# SCH_Emisor.net
KiCad netlist of a schematic drawn in EasyEDA
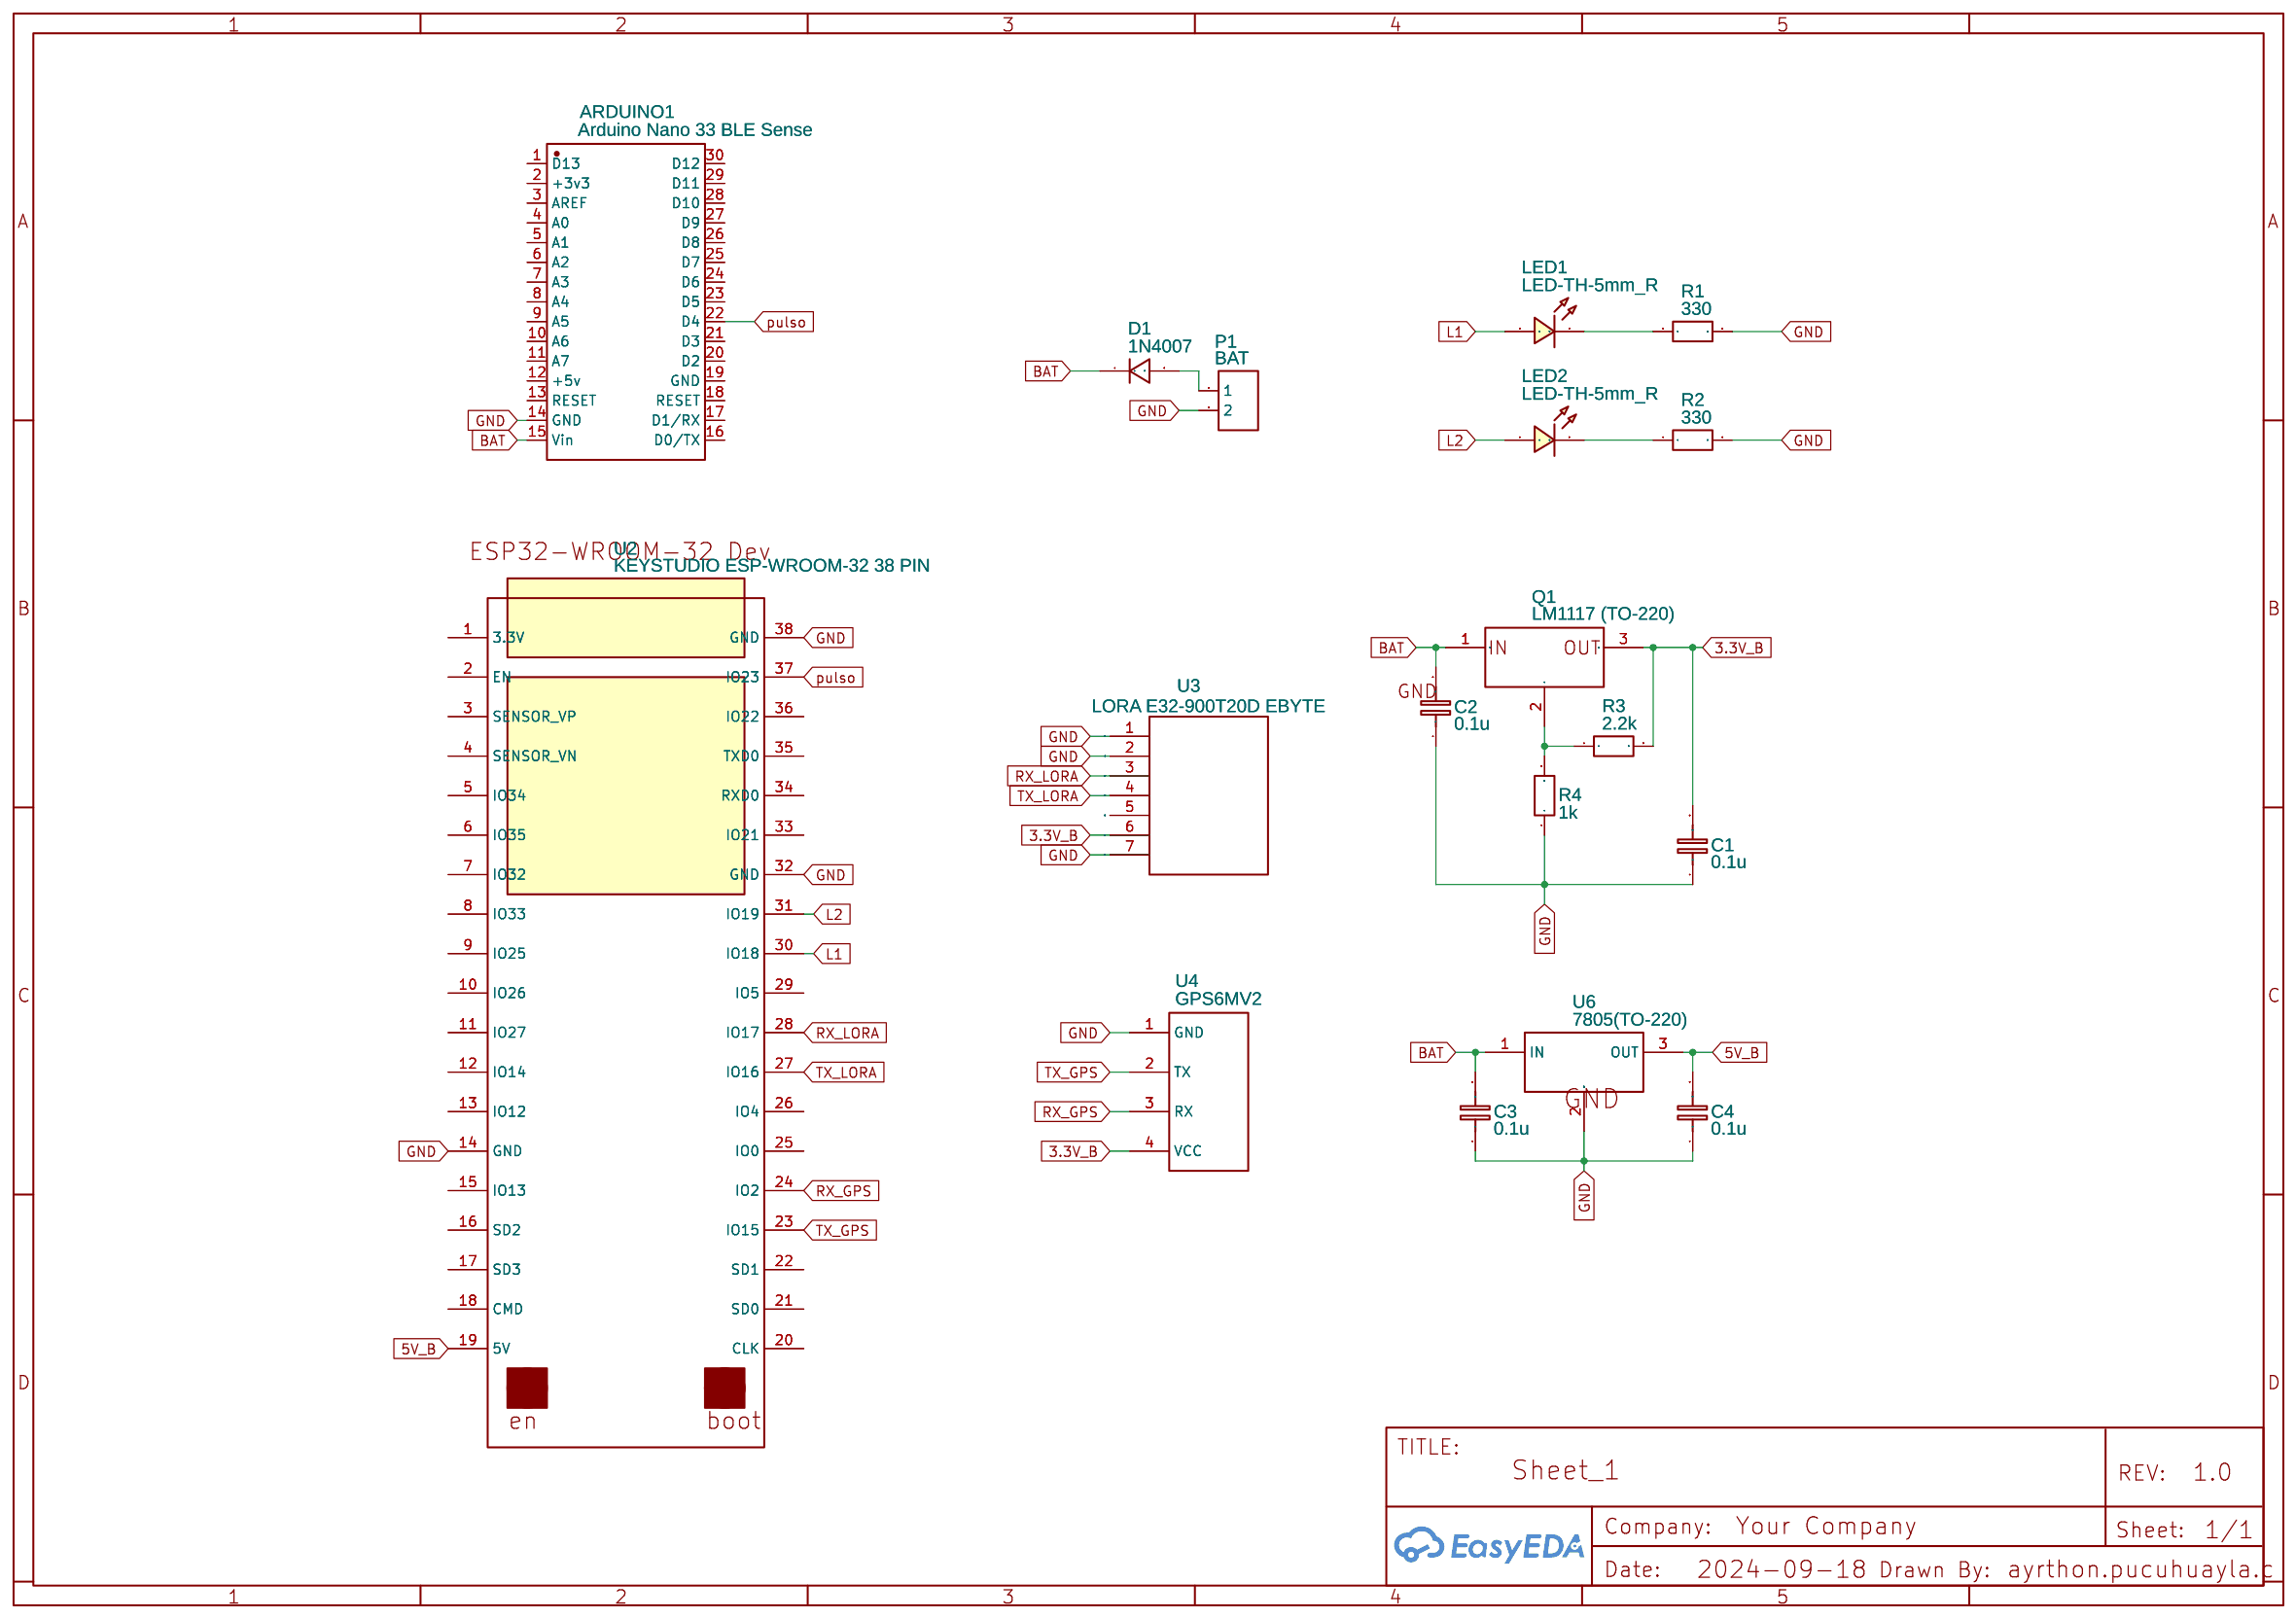
[diagram p0: schematic sheet]

(export (version "E")
  (design (tool "Eeschema 10.0.6"))
  (components
    (comp (ref "ARDUINO1")
      (value "Arduino Nano 33 BLE Sense")
      (libsource (lib "") (part "Arduino Nano 33 BLE Sense"))
    )
    (comp (ref "C1") (value "0.1u") (libsource (lib "") (part "C_RAD-0.1_EU")))
    (comp (ref "C2") (value "0.1u") (libsource (lib "") (part "C_RAD-0.1_EU")))
    (comp (ref "C3") (value "0.1u") (libsource (lib "") (part "C_RAD-0.1_EU")))
    (comp (ref "C4") (value "0.1u") (libsource (lib "") (part "C_RAD-0.1_EU")))
    (comp (ref "D1")
      (value "1N4007")
      (fields (field (name "Manufacturer") "SEMTECH"))
      (libsource (lib "") (part "1N4007"))
    )
    (comp (ref "LED1")
      (value "LED-TH-5mm_R")
      (fields
        (field (name "Manufacturer Part") "333-2SURD/S530-A3")
        (field (name "Manufacturer") "EVERLIGHT(台湾亿光)")
      )
      (libsource (lib "") (part "LED-TH-5mm_R"))
    )
    (comp (ref "LED2")
      (value "LED-TH-5mm_R")
      (fields
        (field (name "Manufacturer Part") "333-2SURD/S530-A3")
        (field (name "Manufacturer") "EVERLIGHT(台湾亿光)")
      )
      (libsource (lib "") (part "LED-TH-5mm_R"))
    )
    (comp (ref "P1") (value "BAT") (libsource (lib "") (part "CONN-TH_2P-P5.00")))
    (comp (ref "Q1") (value "LM1117 (TO-220)") (libsource (lib "") (part "LM1117 (TO-220)")))
    (comp (ref "R1") (value "330") (libsource (lib "") (part "R_AXIAL-0.5_EU")))
    (comp (ref "R2") (value "330") (libsource (lib "") (part "R_AXIAL-0.5_EU")))
    (comp (ref "R3") (value "2.2k") (libsource (lib "") (part "R_AXIAL-0.5_EU")))
    (comp (ref "R4") (value "1k") (libsource (lib "") (part "R_AXIAL-0.5_EU_1")))
    (comp (ref "U2")
      (value "KEYSTUDIO ESP-WROOM-32 38 PIN")
      (libsource (lib "") (part "KEYSTUDIO ESP-WROOM-32 38 PIN"))
    )
    (comp (ref "U3")
      (value "LORA E32-900T20D EBYTE")
      (fields (field (name "Manufacturer") "EBYTE"))
      (libsource (lib "") (part "LORA E32-900T20D EBYTE"))
    )
    (comp (ref "U4") (value "GPS6MV2") (libsource (lib "") (part "GPS6MV2")))
    (comp (ref "U6")
      (value "7805(TO-220)")
      (fields
        (field (name "Manufacturer Part") "L7805CV-DG")
        (field (name "Manufacturer") "STMicroelectronics")
      )
      (libsource (lib "") (part "7805(TO-220)"))
    )
  )
  (nets
    (net (code "1") (name "3.3V_B") (class "Default")
      (node (ref "C1") (pin "2") (pinfunction "2_2") (pintype "unspecified"))
      (node (ref "Q1") (pin "3") (pinfunction "3_3") (pintype "unspecified"))
      (node (ref "R3") (pin "2") (pinfunction "2_2") (pintype "unspecified"))
      (node (ref "U3") (pin "6") (pinfunction "VCC_6") (pintype "unspecified"))
      (node (ref "U4") (pin "4") (pinfunction "VCC_4") (pintype "unspecified"))
    )
    (net (code "2") (name "5V_B") (class "Default")
      (node (ref "C4") (pin "2") (pinfunction "2_2") (pintype "unspecified"))
      (node (ref "U2") (pin "19") (pinfunction "5V_19") (pintype "unspecified"))
      (node (ref "U6") (pin "3") (pinfunction "OUT_3") (pintype "passive"))
    )
    (net (code "3") (name "BAT") (class "Default")
      (node (ref "ARDUINO1") (pin "15") (pinfunction "Vin_15") (pintype "unspecified"))
      (node (ref "C2") (pin "2") (pinfunction "2_2") (pintype "unspecified"))
      (node (ref "C3") (pin "2") (pinfunction "2_2") (pintype "unspecified"))
      (node (ref "D1") (pin "1") (pinfunction "1_1") (pintype "unspecified"))
      (node (ref "Q1") (pin "1") (pinfunction "2_1") (pintype "unspecified"))
      (node (ref "U6") (pin "1") (pinfunction "IN_1") (pintype "passive"))
    )
    (net (code "4") (name "GND") (class "Default")
      (node (ref "ARDUINO1") (pin "14") (pinfunction "GND_14") (pintype "unspecified"))
      (node (ref "C1") (pin "1") (pinfunction "1_1") (pintype "unspecified"))
      (node (ref "C2") (pin "1") (pinfunction "1_1") (pintype "unspecified"))
      (node (ref "C3") (pin "1") (pinfunction "1_1") (pintype "unspecified"))
      (node (ref "C4") (pin "1") (pinfunction "1_1") (pintype "unspecified"))
      (node (ref "P1") (pin "2") (pinfunction "2_2") (pintype "unspecified"))
      (node (ref "R1") (pin "2") (pinfunction "2_2") (pintype "unspecified"))
      (node (ref "R2") (pin "2") (pinfunction "2_2") (pintype "unspecified"))
      (node (ref "R4") (pin "1") (pinfunction "1_1") (pintype "unspecified"))
      (node (ref "U2") (pin "14") (pinfunction "GND_14") (pintype "unspecified"))
      (node (ref "U2") (pin "32") (pinfunction "GND_32") (pintype "unspecified"))
      (node (ref "U2") (pin "38") (pinfunction "GND_38") (pintype "unspecified"))
      (node (ref "U3") (pin "1") (pinfunction "M0_1") (pintype "unspecified"))
      (node (ref "U3") (pin "2") (pinfunction "M1_2") (pintype "unspecified"))
      (node (ref "U3") (pin "7") (pinfunction "GND_7") (pintype "unspecified"))
      (node (ref "U4") (pin "1") (pinfunction "GND_1") (pintype "unspecified"))
      (node (ref "U6") (pin "2") (pinfunction "GND_2") (pintype "passive"))
    )
    (net (code "5") (name "L1") (class "Default")
      (node (ref "LED1") (pin "1") (pinfunction "1_1") (pintype "unspecified"))
      (node (ref "U2") (pin "30") (pinfunction "IO18_30") (pintype "unspecified"))
    )
    (net (code "6") (name "L2") (class "Default")
      (node (ref "LED2") (pin "1") (pinfunction "1_1") (pintype "unspecified"))
      (node (ref "U2") (pin "31") (pinfunction "IO19_31") (pintype "unspecified"))
    )
    (net (code "7") (name "Net-(D1-Pad2)") (class "Default")
      (node (ref "D1") (pin "2") (pinfunction "2_2") (pintype "unspecified"))
      (node (ref "P1") (pin "1") (pinfunction "1_1") (pintype "unspecified"))
    )
    (net (code "8") (name "Net-(LED1-Pad2)") (class "Default")
      (node (ref "LED1") (pin "2") (pinfunction "2_2") (pintype "unspecified"))
      (node (ref "R1") (pin "1") (pinfunction "1_1") (pintype "unspecified"))
    )
    (net (code "9") (name "Net-(LED2-Pad2)") (class "Default")
      (node (ref "LED2") (pin "2") (pinfunction "2_2") (pintype "unspecified"))
      (node (ref "R2") (pin "1") (pinfunction "1_1") (pintype "unspecified"))
    )
    (net (code "10") (name "Net-(Q1-1)") (class "Default")
      (node (ref "Q1") (pin "2") (pinfunction "1_2") (pintype "unspecified"))
      (node (ref "R3") (pin "1") (pinfunction "1_1") (pintype "unspecified"))
      (node (ref "R4") (pin "2") (pinfunction "2_2") (pintype "unspecified"))
    )
    (net (code "11") (name "RX_GPS") (class "Default")
      (node (ref "U2") (pin "24") (pinfunction "IO2_24") (pintype "unspecified"))
      (node (ref "U4") (pin "3") (pinfunction "RX_3") (pintype "unspecified"))
    )
    (net (code "12") (name "RX_LORA") (class "Default")
      (node (ref "U2") (pin "28") (pinfunction "IO17_28") (pintype "unspecified"))
      (node (ref "U3") (pin "3") (pinfunction "RXD_3") (pintype "unspecified"))
    )
    (net (code "13") (name "TX_GPS") (class "Default")
      (node (ref "U2") (pin "23") (pinfunction "IO15_23") (pintype "unspecified"))
      (node (ref "U4") (pin "2") (pinfunction "TX_2") (pintype "unspecified"))
    )
    (net (code "14") (name "TX_LORA") (class "Default")
      (node (ref "U2") (pin "27") (pinfunction "IO16_27") (pintype "unspecified"))
      (node (ref "U3") (pin "4") (pinfunction "TXD_4") (pintype "unspecified"))
    )
    (net (code "15") (name "pulso") (class "Default")
      (node (ref "ARDUINO1") (pin "22") (pinfunction "D4_22") (pintype "unspecified"))
      (node (ref "U2") (pin "37") (pinfunction "IO23_37") (pintype "unspecified"))
    )
    (net (code "16") (name "unconnected-(ARDUINO1-+3v3-Pad2)") (class "Default")
      (node (ref "ARDUINO1") (pin "2") (pinfunction "+3v3_2") (pintype "unspecified"))
    )
    (net (code "17") (name "unconnected-(ARDUINO1-+5v-Pad12)") (class "Default")
      (node (ref "ARDUINO1") (pin "12") (pinfunction "+5v_12") (pintype "unspecified"))
    )
    (net (code "18") (name "unconnected-(ARDUINO1-A0-Pad4)") (class "Default")
      (node (ref "ARDUINO1") (pin "4") (pinfunction "A0_4") (pintype "unspecified"))
    )
    (net (code "19") (name "unconnected-(ARDUINO1-A1-Pad5)") (class "Default")
      (node (ref "ARDUINO1") (pin "5") (pinfunction "A1_5") (pintype "unspecified"))
    )
    (net (code "20") (name "unconnected-(ARDUINO1-A2-Pad6)") (class "Default")
      (node (ref "ARDUINO1") (pin "6") (pinfunction "A2_6") (pintype "unspecified"))
    )
    (net (code "21") (name "unconnected-(ARDUINO1-A3-Pad7)") (class "Default")
      (node (ref "ARDUINO1") (pin "7") (pinfunction "A3_7") (pintype "unspecified"))
    )
    (net (code "22") (name "unconnected-(ARDUINO1-A4-Pad8)") (class "Default")
      (node (ref "ARDUINO1") (pin "8") (pinfunction "A4_8") (pintype "unspecified"))
    )
    (net (code "23") (name "unconnected-(ARDUINO1-A5-Pad9)") (class "Default")
      (node (ref "ARDUINO1") (pin "9") (pinfunction "A5_9") (pintype "unspecified"))
    )
    (net (code "24") (name "unconnected-(ARDUINO1-A6-Pad10)") (class "Default")
      (node (ref "ARDUINO1") (pin "10") (pinfunction "A6_10") (pintype "unspecified"))
    )
    (net (code "25") (name "unconnected-(ARDUINO1-A7-Pad11)") (class "Default")
      (node (ref "ARDUINO1") (pin "11") (pinfunction "A7_11") (pintype "unspecified"))
    )
    (net (code "26") (name "unconnected-(ARDUINO1-AREF-Pad3)") (class "Default")
      (node (ref "ARDUINO1") (pin "3") (pinfunction "AREF_3") (pintype "unspecified"))
    )
    (net (code "27") (name "unconnected-(ARDUINO1-D0{slash}TX-Pad16)") (class "Default")
      (node (ref "ARDUINO1") (pin "16") (pinfunction "D0/TX_16") (pintype "unspecified"))
    )
    (net (code "28") (name "unconnected-(ARDUINO1-D1{slash}RX-Pad17)") (class "Default")
      (node (ref "ARDUINO1") (pin "17") (pinfunction "D1/RX_17") (pintype "unspecified"))
    )
    (net (code "29") (name "unconnected-(ARDUINO1-D2-Pad20)") (class "Default")
      (node (ref "ARDUINO1") (pin "20") (pinfunction "D2_20") (pintype "unspecified"))
    )
    (net (code "30") (name "unconnected-(ARDUINO1-D3-Pad21)") (class "Default")
      (node (ref "ARDUINO1") (pin "21") (pinfunction "D3_21") (pintype "unspecified"))
    )
    (net (code "31") (name "unconnected-(ARDUINO1-D5-Pad23)") (class "Default")
      (node (ref "ARDUINO1") (pin "23") (pinfunction "D5_23") (pintype "unspecified"))
    )
    (net (code "32") (name "unconnected-(ARDUINO1-D6-Pad24)") (class "Default")
      (node (ref "ARDUINO1") (pin "24") (pinfunction "D6_24") (pintype "unspecified"))
    )
    (net (code "33") (name "unconnected-(ARDUINO1-D7-Pad25)") (class "Default")
      (node (ref "ARDUINO1") (pin "25") (pinfunction "D7_25") (pintype "unspecified"))
    )
    (net (code "34") (name "unconnected-(ARDUINO1-D8-Pad26)") (class "Default")
      (node (ref "ARDUINO1") (pin "26") (pinfunction "D8_26") (pintype "unspecified"))
    )
    (net (code "35") (name "unconnected-(ARDUINO1-D9-Pad27)") (class "Default")
      (node (ref "ARDUINO1") (pin "27") (pinfunction "D9_27") (pintype "unspecified"))
    )
    (net (code "36") (name "unconnected-(ARDUINO1-D10-Pad28)") (class "Default")
      (node (ref "ARDUINO1") (pin "28") (pinfunction "D10_28") (pintype "unspecified"))
    )
    (net (code "37") (name "unconnected-(ARDUINO1-D11-Pad29)") (class "Default")
      (node (ref "ARDUINO1") (pin "29") (pinfunction "D11_29") (pintype "unspecified"))
    )
    (net (code "38") (name "unconnected-(ARDUINO1-D12-Pad30)") (class "Default")
      (node (ref "ARDUINO1") (pin "30") (pinfunction "D12_30") (pintype "unspecified"))
    )
    (net (code "39") (name "unconnected-(ARDUINO1-D13-Pad1)") (class "Default")
      (node (ref "ARDUINO1") (pin "1") (pinfunction "D13_1") (pintype "unspecified"))
    )
    (net (code "40") (name "unconnected-(ARDUINO1-GND-Pad19)") (class "Default")
      (node (ref "ARDUINO1") (pin "19") (pinfunction "GND_19") (pintype "unspecified"))
    )
    (net (code "41") (name "unconnected-(ARDUINO1-RESET-Pad13)") (class "Default")
      (node (ref "ARDUINO1") (pin "13") (pinfunction "RESET_13") (pintype "unspecified"))
    )
    (net (code "42") (name "unconnected-(ARDUINO1-RESET-Pad18)") (class "Default")
      (node (ref "ARDUINO1") (pin "18") (pinfunction "RESET_18") (pintype "unspecified"))
    )
    (net (code "43") (name "unconnected-(U2-3.3V-Pad1)") (class "Default")
      (node (ref "U2") (pin "1") (pinfunction "3.3V_1") (pintype "unspecified"))
    )
    (net (code "44") (name "unconnected-(U2-CLK-Pad20)") (class "Default")
      (node (ref "U2") (pin "20") (pinfunction "CLK_20") (pintype "unspecified"))
    )
    (net (code "45") (name "unconnected-(U2-CMD-Pad18)") (class "Default")
      (node (ref "U2") (pin "18") (pinfunction "CMD_18") (pintype "unspecified"))
    )
    (net (code "46") (name "unconnected-(U2-EN-Pad2)") (class "Default")
      (node (ref "U2") (pin "2") (pinfunction "EN_2") (pintype "unspecified"))
    )
    (net (code "47") (name "unconnected-(U2-IO0-Pad25)") (class "Default")
      (node (ref "U2") (pin "25") (pinfunction "IO0_25") (pintype "unspecified"))
    )
    (net (code "48") (name "unconnected-(U2-IO4-Pad26)") (class "Default")
      (node (ref "U2") (pin "26") (pinfunction "IO4_26") (pintype "unspecified"))
    )
    (net (code "49") (name "unconnected-(U2-IO5-Pad29)") (class "Default")
      (node (ref "U2") (pin "29") (pinfunction "IO5_29") (pintype "unspecified"))
    )
    (net (code "50") (name "unconnected-(U2-IO12-Pad13)") (class "Default")
      (node (ref "U2") (pin "13") (pinfunction "IO12_13") (pintype "unspecified"))
    )
    (net (code "51") (name "unconnected-(U2-IO13-Pad15)") (class "Default")
      (node (ref "U2") (pin "15") (pinfunction "IO13_15") (pintype "unspecified"))
    )
    (net (code "52") (name "unconnected-(U2-IO14-Pad12)") (class "Default")
      (node (ref "U2") (pin "12") (pinfunction "IO14_12") (pintype "unspecified"))
    )
    (net (code "53") (name "unconnected-(U2-IO21-Pad33)") (class "Default")
      (node (ref "U2") (pin "33") (pinfunction "IO21_33") (pintype "unspecified"))
    )
    (net (code "54") (name "unconnected-(U2-IO22-Pad36)") (class "Default")
      (node (ref "U2") (pin "36") (pinfunction "IO22_36") (pintype "unspecified"))
    )
    (net (code "55") (name "unconnected-(U2-IO25-Pad9)") (class "Default")
      (node (ref "U2") (pin "9") (pinfunction "IO25_9") (pintype "unspecified"))
    )
    (net (code "56") (name "unconnected-(U2-IO26-Pad10)") (class "Default")
      (node (ref "U2") (pin "10") (pinfunction "IO26_10") (pintype "unspecified"))
    )
    (net (code "57") (name "unconnected-(U2-IO27-Pad11)") (class "Default")
      (node (ref "U2") (pin "11") (pinfunction "IO27_11") (pintype "unspecified"))
    )
    (net (code "58") (name "unconnected-(U2-IO32-Pad7)") (class "Default")
      (node (ref "U2") (pin "7") (pinfunction "IO32_7") (pintype "unspecified"))
    )
    (net (code "59") (name "unconnected-(U2-IO33-Pad8)") (class "Default")
      (node (ref "U2") (pin "8") (pinfunction "IO33_8") (pintype "unspecified"))
    )
    (net (code "60") (name "unconnected-(U2-IO34-Pad5)") (class "Default")
      (node (ref "U2") (pin "5") (pinfunction "IO34_5") (pintype "unspecified"))
    )
    (net (code "61") (name "unconnected-(U2-IO35-Pad6)") (class "Default")
      (node (ref "U2") (pin "6") (pinfunction "IO35_6") (pintype "unspecified"))
    )
    (net (code "62") (name "unconnected-(U2-RXD0-Pad34)") (class "Default")
      (node (ref "U2") (pin "34") (pinfunction "RXD0_34") (pintype "unspecified"))
    )
    (net (code "63") (name "unconnected-(U2-SD0-Pad21)") (class "Default")
      (node (ref "U2") (pin "21") (pinfunction "SD0_21") (pintype "unspecified"))
    )
    (net (code "64") (name "unconnected-(U2-SD1-Pad22)") (class "Default")
      (node (ref "U2") (pin "22") (pinfunction "SD1_22") (pintype "unspecified"))
    )
    (net (code "65") (name "unconnected-(U2-SD2-Pad16)") (class "Default")
      (node (ref "U2") (pin "16") (pinfunction "SD2_16") (pintype "unspecified"))
    )
    (net (code "66") (name "unconnected-(U2-SD3-Pad17)") (class "Default")
      (node (ref "U2") (pin "17") (pinfunction "SD3_17") (pintype "unspecified"))
    )
    (net (code "67") (name "unconnected-(U2-SENSOR_VN-Pad4)") (class "Default")
      (node (ref "U2") (pin "4") (pinfunction "SENSOR_VN_4") (pintype "unspecified"))
    )
    (net (code "68") (name "unconnected-(U2-SENSOR_VP-Pad3)") (class "Default")
      (node (ref "U2") (pin "3") (pinfunction "SENSOR_VP_3") (pintype "unspecified"))
    )
    (net (code "69") (name "unconnected-(U2-TXD0-Pad35)") (class "Default")
      (node (ref "U2") (pin "35") (pinfunction "TXD0_35") (pintype "unspecified"))
    )
    (net (code "70") (name "unconnected-(U3-AUX-Pad5)") (class "Default")
      (node (ref "U3") (pin "5") (pinfunction "AUX_5") (pintype "unspecified"))
    )
  )
)
